# IZU2023_computerboard_ver3.net
KiCad netlist of a schematic drawn in EAGLE
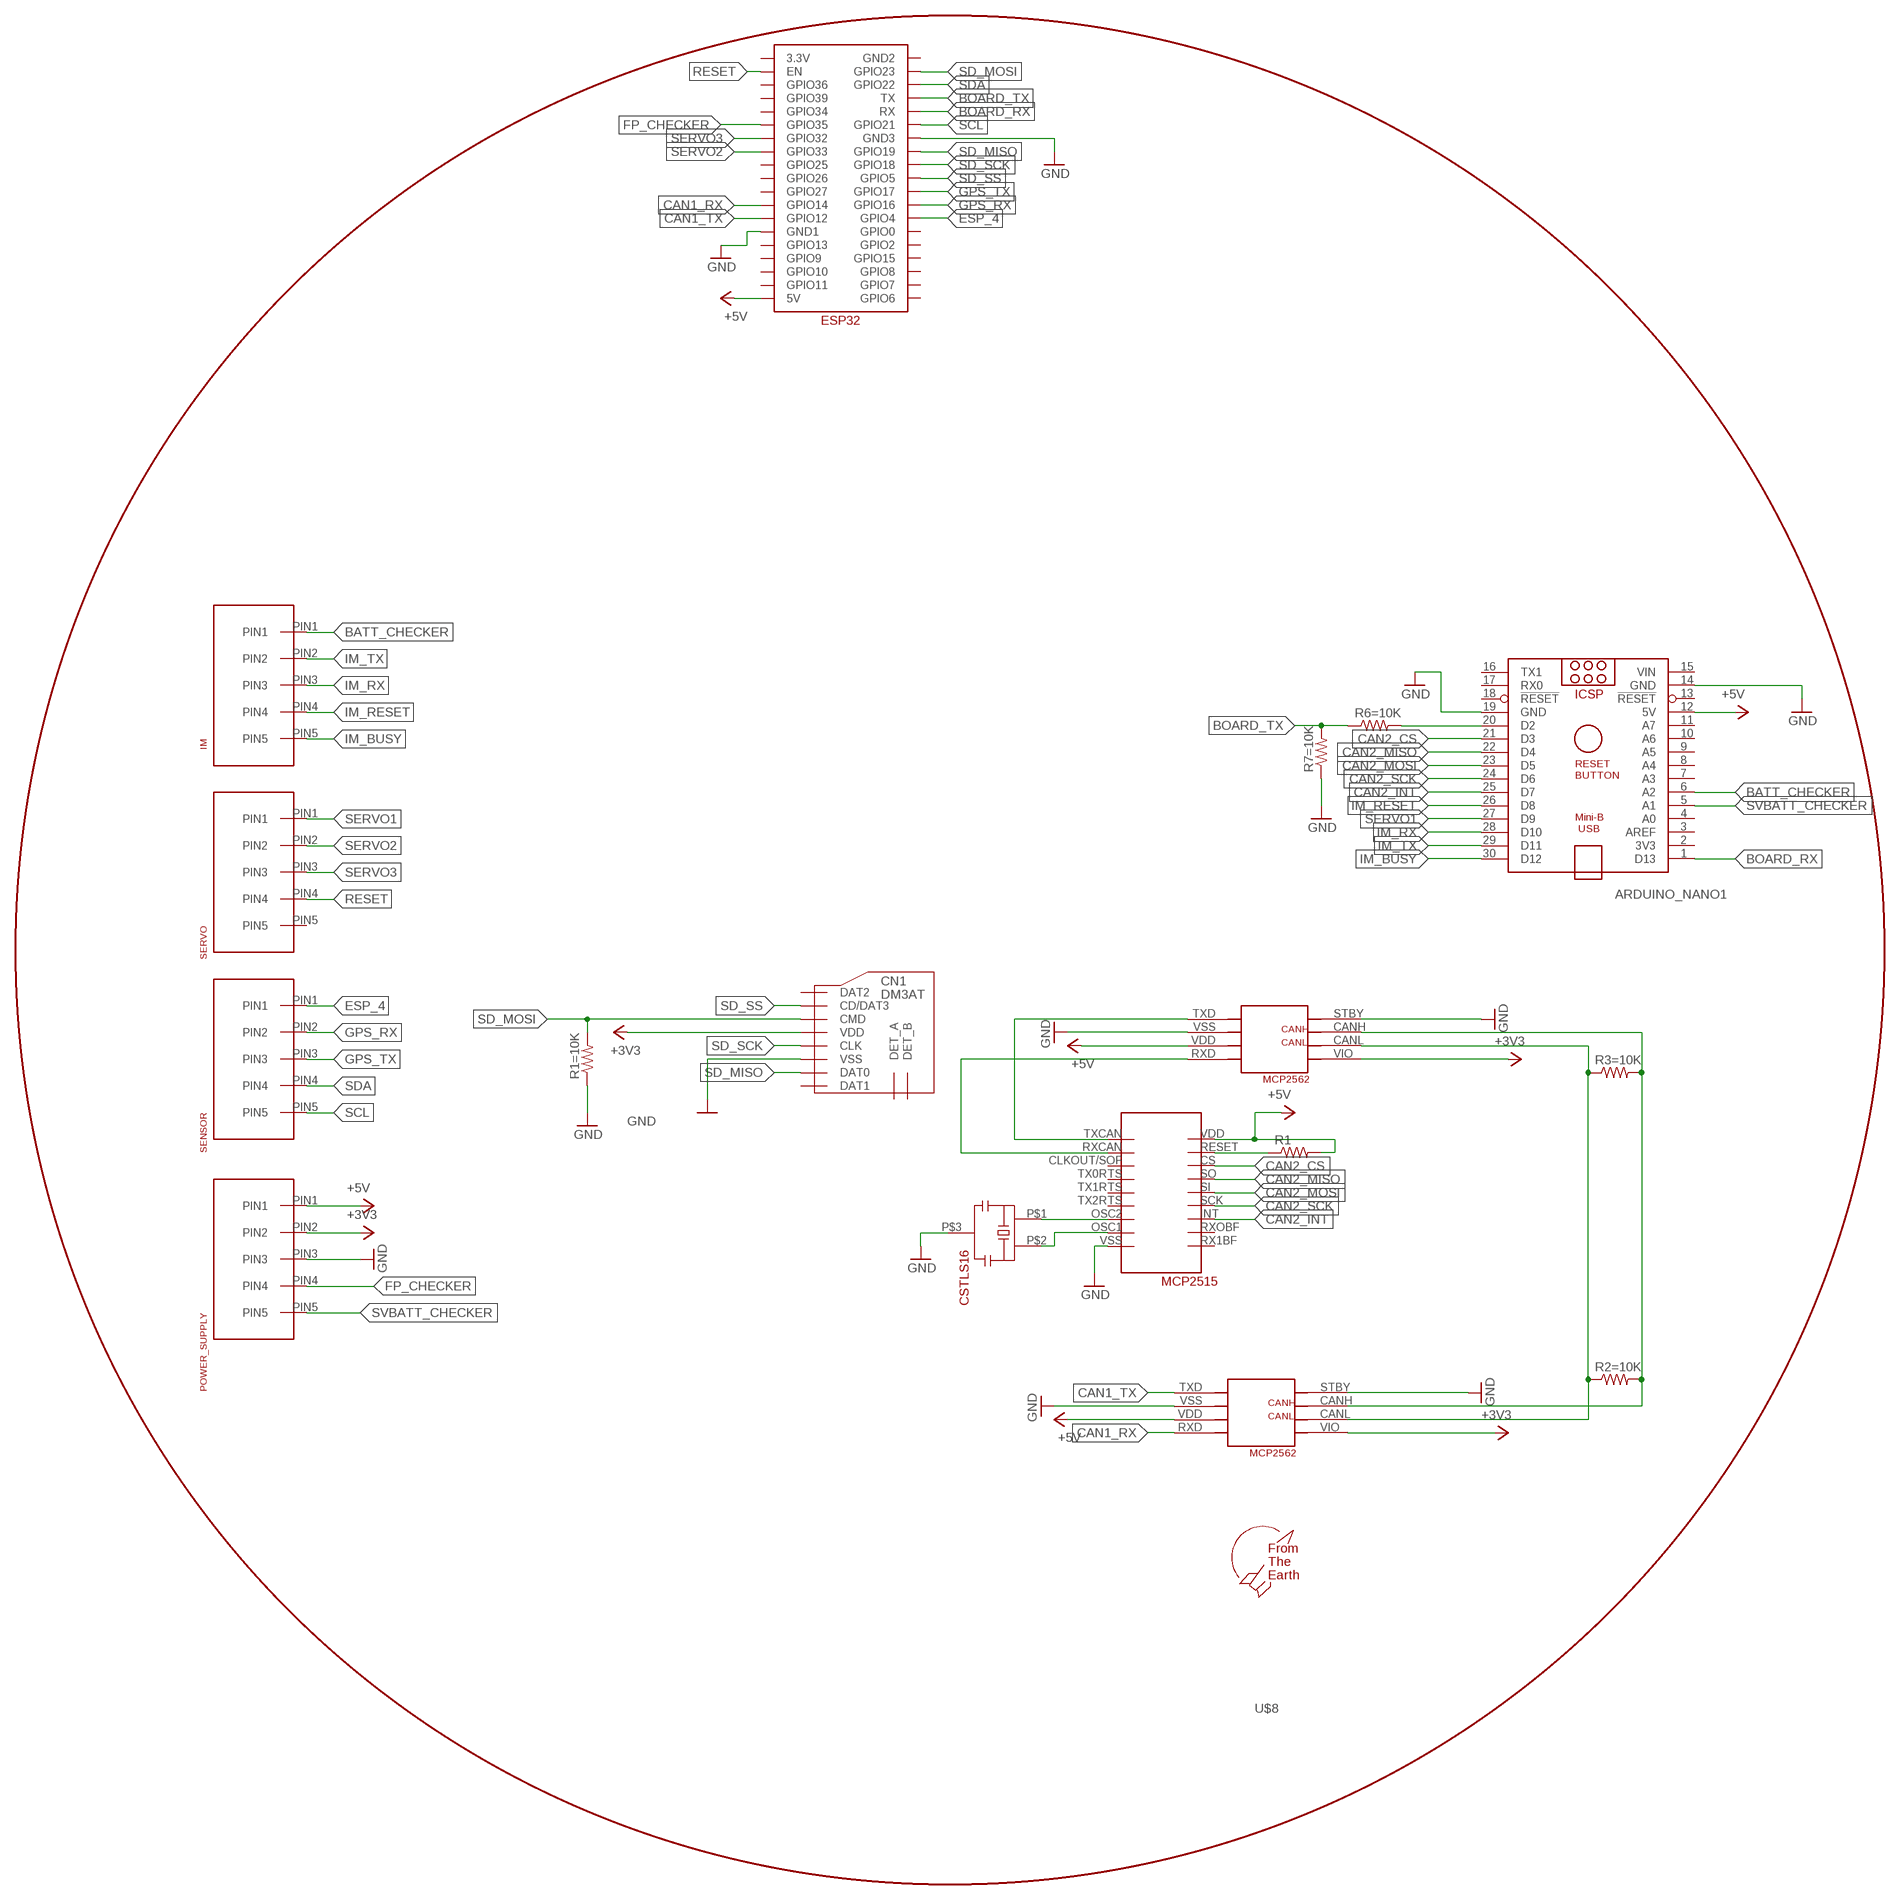
[diagram p0: schematic, sheet 1]

(export (version "E")
  (design (tool "Eeschema 10.0.6"))
  (components
    (comp (ref "ARDUINO_NANO1")
      (value "ARDUINO_NANO")
      (footprint "eagle-import:ARDUINO_NANO")
      (libsource (lib "eagle-import") (part "ARDUINO_NANO"))
    )
    (comp (ref "CN1")
      (value "DM3AT")
      (footprint "eagle-import:DM3AT")
      (libsource (lib "eagle-import") (part "DM3AT"))
    )
    (comp (ref "IM")
      (value "5PIN")
      (footprint "eagle-import:5PIN")
      (libsource (lib "eagle-import") (part "5PIN"))
    )
    (comp (ref "POWER_SUPPLY")
      (value "5PIN")
      (footprint "eagle-import:5PIN")
      (libsource (lib "eagle-import") (part "5PIN"))
    )
    (comp (ref "R1")
      (value "R-US_0204/7")
      (footprint "eagle-import:0204_7")
      (libsource (lib "eagle-import") (part "R-US_0204/7"))
    )
    (comp (ref "R1=10K")
      (value "R-US_0204/7")
      (footprint "eagle-import:0204_7")
      (libsource (lib "eagle-import") (part "R-US_0204/7"))
    )
    (comp (ref "R2=10K")
      (value "R-US_0204/7")
      (footprint "eagle-import:0204_7")
      (libsource (lib "eagle-import") (part "R-US_0204/7"))
    )
    (comp (ref "R3=10K")
      (value "R-US_0204/7")
      (footprint "eagle-import:0204_7")
      (libsource (lib "eagle-import") (part "R-US_0204/7"))
    )
    (comp (ref "R6=10K")
      (value "R-US_0204/7")
      (footprint "eagle-import:0204_7")
      (libsource (lib "eagle-import") (part "R-US_0204/7"))
    )
    (comp (ref "R7=10K")
      (value "R-US_0204/7")
      (footprint "eagle-import:0204_7")
      (libsource (lib "eagle-import") (part "R-US_0204/7"))
    )
    (comp (ref "SENSOR")
      (value "5PIN")
      (footprint "eagle-import:5PIN")
      (libsource (lib "eagle-import") (part "5PIN"))
    )
    (comp (ref "SERVO")
      (value "5PIN")
      (footprint "eagle-import:5PIN")
      (libsource (lib "eagle-import") (part "5PIN"))
    )
    (comp (ref "U$2")
      (value "MCP2515")
      (footprint "eagle-import:MCP2515")
      (libsource (lib "eagle-import") (part "MCP2515"))
    )
    (comp (ref "U$3")
      (value "MCP2562")
      (footprint "eagle-import:MCP2562")
      (libsource (lib "eagle-import") (part "MCP2562"))
    )
    (comp (ref "U$4")
      (value "MCP2562")
      (footprint "eagle-import:MCP2562")
      (libsource (lib "eagle-import") (part "MCP2562"))
    )
    (comp (ref "U$5")
      (value "CSTLS16")
      (footprint "eagle-import:CSTLS16")
      (libsource (lib "eagle-import") (part "CSTLS16"))
    )
    (comp (ref "U$7")
      (value "ESP32_ESP32")
      (footprint "eagle-import:ESP32_ESP32")
      (libsource (lib "eagle-import") (part "ESP32_ESP32"))
    )
    (comp (ref "U$8")
      (value "F.T.E.LOGO")
      (footprint "eagle-import:LOGO")
      (libsource (lib "eagle-import") (part "F.T.E.LOGO"))
    )
  )
  (nets
    (net (code "1") (name "+3V3") (class "Default")
      (node (ref "CN1") (pin "VDD") (pinfunction "VDD_VDD") (pintype "bidirectional"))
      (node (ref "POWER_SUPPLY") (pin "PIN2") (pinfunction "PIN2_PIN2") (pintype "bidirectional"))
      (node (ref "U$3") (pin "VIO") (pinfunction "VIO_VIO") (pintype "bidirectional"))
      (node (ref "U$4") (pin "VIO") (pinfunction "VIO_VIO") (pintype "bidirectional"))
    )
    (net (code "2") (name "+5V") (class "Default")
      (node (ref "ARDUINO_NANO1") (pin "12") (pinfunction "5V_12") (pintype "power_in"))
      (node (ref "POWER_SUPPLY") (pin "PIN1") (pinfunction "PIN1_PIN1") (pintype "bidirectional"))
      (node (ref "R1") (pin "2") (pinfunction "2_2") (pintype "passive"))
      (node (ref "U$2") (pin "VDD") (pinfunction "VDD_VDD") (pintype "bidirectional"))
      (node (ref "U$3") (pin "VDD") (pinfunction "VDD_VDD") (pintype "bidirectional"))
      (node (ref "U$4") (pin "VDD") (pinfunction "VDD_VDD") (pintype "bidirectional"))
      (node (ref "U$7") (pin "5V") (pinfunction "5V_5V") (pintype "bidirectional"))
    )
    (net (code "3") (name "/VIN") (class "Default")
      (node (ref "ARDUINO_NANO1") (pin "15") (pinfunction "VIN_15") (pintype "power_in"))
    )
    (net (code "4") (name "BATT_CHECKER") (class "Default")
      (node (ref "ARDUINO_NANO1") (pin "6") (pinfunction "A2_6") (pintype "bidirectional"))
      (node (ref "IM") (pin "PIN1") (pinfunction "PIN1_PIN1") (pintype "bidirectional"))
    )
    (net (code "5") (name "BOARD_RX") (class "Default")
      (node (ref "ARDUINO_NANO1") (pin "1") (pinfunction "D13_1") (pintype "bidirectional"))
      (node (ref "U$7") (pin "RX") (pinfunction "RX_RX") (pintype "bidirectional"))
    )
    (net (code "6") (name "BOARD_TX") (class "Default")
      (node (ref "R6=10K") (pin "1") (pinfunction "1_1") (pintype "passive"))
      (node (ref "R7=10K") (pin "2") (pinfunction "2_2") (pintype "passive"))
      (node (ref "U$7") (pin "TX") (pinfunction "TX_TX") (pintype "bidirectional"))
    )
    (net (code "7") (name "CAN1_RX") (class "Default")
      (node (ref "U$3") (pin "RXD") (pinfunction "RXD_RXD") (pintype "bidirectional"))
      (node (ref "U$7") (pin "GPIO14") (pinfunction "GPIO14_GPIO14") (pintype "bidirectional"))
    )
    (net (code "8") (name "CAN1_TX") (class "Default")
      (node (ref "U$3") (pin "TXD") (pinfunction "TXD_TXD") (pintype "bidirectional"))
      (node (ref "U$7") (pin "GPIO12") (pinfunction "GPIO12_GPIO12") (pintype "bidirectional"))
    )
    (net (code "9") (name "CAN2_CS") (class "Default")
      (node (ref "ARDUINO_NANO1") (pin "21") (pinfunction "D3_21") (pintype "bidirectional"))
      (node (ref "U$2") (pin "CS") (pinfunction "CS_CS") (pintype "bidirectional"))
    )
    (net (code "10") (name "CAN2_INT") (class "Default")
      (node (ref "ARDUINO_NANO1") (pin "25") (pinfunction "D7_25") (pintype "bidirectional"))
      (node (ref "U$2") (pin "INT") (pinfunction "INT_INT") (pintype "bidirectional"))
    )
    (net (code "11") (name "CAN2_MISO") (class "Default")
      (node (ref "ARDUINO_NANO1") (pin "22") (pinfunction "D4_22") (pintype "bidirectional"))
      (node (ref "U$2") (pin "SO") (pinfunction "SO_SO") (pintype "bidirectional"))
    )
    (net (code "12") (name "CAN2_MOSI") (class "Default")
      (node (ref "ARDUINO_NANO1") (pin "23") (pinfunction "D5_23") (pintype "bidirectional"))
      (node (ref "U$2") (pin "SI") (pinfunction "SI_SI") (pintype "bidirectional"))
    )
    (net (code "13") (name "CAN2_SCK") (class "Default")
      (node (ref "ARDUINO_NANO1") (pin "24") (pinfunction "D6_24") (pintype "bidirectional"))
      (node (ref "U$2") (pin "SCK") (pinfunction "SCK_SCK") (pintype "bidirectional"))
    )
    (net (code "14") (name "ESP_4") (class "Default")
      (node (ref "SENSOR") (pin "PIN1") (pinfunction "PIN1_PIN1") (pintype "bidirectional"))
      (node (ref "U$7") (pin "GPIO4") (pinfunction "GPIO4_GPIO4") (pintype "bidirectional"))
    )
    (net (code "15") (name "FP_CHECKER") (class "Default")
      (node (ref "POWER_SUPPLY") (pin "PIN4") (pinfunction "PIN4_PIN4") (pintype "bidirectional"))
      (node (ref "U$7") (pin "GPIO35") (pinfunction "GPIO35_GPIO35") (pintype "bidirectional"))
    )
    (net (code "16") (name "GND") (class "Default")
      (node (ref "ARDUINO_NANO1") (pin "14") (pinfunction "GND_14") (pintype "power_in"))
      (node (ref "ARDUINO_NANO1") (pin "19") (pinfunction "GND_19") (pintype "power_in"))
      (node (ref "CN1") (pin "VSS") (pinfunction "VSS_VSS") (pintype "bidirectional"))
      (node (ref "POWER_SUPPLY") (pin "PIN3") (pinfunction "PIN3_PIN3") (pintype "bidirectional"))
      (node (ref "R1=10K") (pin "1") (pinfunction "1_1") (pintype "passive"))
      (node (ref "R7=10K") (pin "1") (pinfunction "1_1") (pintype "passive"))
      (node (ref "U$2") (pin "VSS") (pinfunction "VSS_VSS") (pintype "bidirectional"))
      (node (ref "U$3") (pin "STBY") (pinfunction "STBY_STBY") (pintype "bidirectional"))
      (node (ref "U$3") (pin "VSS") (pinfunction "VSS_VSS") (pintype "bidirectional"))
      (node (ref "U$4") (pin "STBY") (pinfunction "STBY_STBY") (pintype "bidirectional"))
      (node (ref "U$4") (pin "VSS") (pinfunction "VSS_VSS") (pintype "bidirectional"))
      (node (ref "U$5") (pin "P$3") (pinfunction "P$3_P$3") (pintype "bidirectional"))
      (node (ref "U$7") (pin "GND1") (pinfunction "GND1_GND1") (pintype "bidirectional"))
      (node (ref "U$7") (pin "GND3") (pinfunction "GND3_GND3") (pintype "bidirectional"))
    )
    (net (code "17") (name "GPS_RX") (class "Default")
      (node (ref "SENSOR") (pin "PIN2") (pinfunction "PIN2_PIN2") (pintype "bidirectional"))
      (node (ref "U$7") (pin "GPIO16") (pinfunction "GPIO16_GPIO16") (pintype "bidirectional"))
    )
    (net (code "18") (name "GPS_TX") (class "Default")
      (node (ref "SENSOR") (pin "PIN3") (pinfunction "PIN3_PIN3") (pintype "bidirectional"))
      (node (ref "U$7") (pin "GPIO17") (pinfunction "GPIO17_GPIO17") (pintype "bidirectional"))
    )
    (net (code "19") (name "IM_BUSY") (class "Default")
      (node (ref "ARDUINO_NANO1") (pin "30") (pinfunction "D12_30") (pintype "bidirectional"))
      (node (ref "IM") (pin "PIN5") (pinfunction "PIN5_PIN5") (pintype "bidirectional"))
    )
    (net (code "20") (name "IM_RESET") (class "Default")
      (node (ref "ARDUINO_NANO1") (pin "26") (pinfunction "D8_26") (pintype "bidirectional"))
      (node (ref "IM") (pin "PIN4") (pinfunction "PIN4_PIN4") (pintype "bidirectional"))
    )
    (net (code "21") (name "IM_RX") (class "Default")
      (node (ref "ARDUINO_NANO1") (pin "28") (pinfunction "D10_28") (pintype "bidirectional"))
      (node (ref "IM") (pin "PIN3") (pinfunction "PIN3_PIN3") (pintype "bidirectional"))
    )
    (net (code "22") (name "IM_TX") (class "Default")
      (node (ref "ARDUINO_NANO1") (pin "29") (pinfunction "D11_29") (pintype "bidirectional"))
      (node (ref "IM") (pin "PIN2") (pinfunction "PIN2_PIN2") (pintype "bidirectional"))
    )
    (net (code "23") (name "Net-(ARDUINO_NANO1-D2)") (class "Default")
      (node (ref "ARDUINO_NANO1") (pin "20") (pinfunction "D2_20") (pintype "bidirectional"))
      (node (ref "R6=10K") (pin "2") (pinfunction "2_2") (pintype "passive"))
    )
    (net (code "24") (name "Net-(R1-Pad1)") (class "Default")
      (node (ref "R1") (pin "1") (pinfunction "1_1") (pintype "passive"))
      (node (ref "U$2") (pin "RESET") (pinfunction "RESET_RESET") (pintype "bidirectional"))
    )
    (net (code "25") (name "Net-(R2=10K-Pad1)") (class "Default")
      (node (ref "R2=10K") (pin "1") (pinfunction "1_1") (pintype "passive"))
      (node (ref "R3=10K") (pin "1") (pinfunction "1_1") (pintype "passive"))
      (node (ref "U$3") (pin "CANL") (pinfunction "CANL_CANL") (pintype "bidirectional"))
      (node (ref "U$4") (pin "CANL") (pinfunction "CANL_CANL") (pintype "bidirectional"))
    )
    (net (code "26") (name "Net-(R2=10K-Pad2)") (class "Default")
      (node (ref "R2=10K") (pin "2") (pinfunction "2_2") (pintype "passive"))
      (node (ref "R3=10K") (pin "2") (pinfunction "2_2") (pintype "passive"))
      (node (ref "U$3") (pin "CANH") (pinfunction "CANH_CANH") (pintype "bidirectional"))
      (node (ref "U$4") (pin "CANH") (pinfunction "CANH_CANH") (pintype "bidirectional"))
    )
    (net (code "27") (name "Net-(U$2-PadOSC1)") (class "Default")
      (node (ref "U$2") (pin "OSC1") (pinfunction "OSC1_OSC1") (pintype "bidirectional"))
      (node (ref "U$5") (pin "P$2") (pinfunction "P$2_P$2") (pintype "bidirectional"))
    )
    (net (code "28") (name "Net-(U$2-PadOSC2)") (class "Default")
      (node (ref "U$2") (pin "OSC2") (pinfunction "OSC2_OSC2") (pintype "bidirectional"))
      (node (ref "U$5") (pin "P$1") (pinfunction "P$1_P$1") (pintype "bidirectional"))
    )
    (net (code "29") (name "Net-(U$2-PadRXCAN)") (class "Default")
      (node (ref "U$2") (pin "RXCAN") (pinfunction "RXCAN_RXCAN") (pintype "bidirectional"))
      (node (ref "U$4") (pin "RXD") (pinfunction "RXD_RXD") (pintype "bidirectional"))
    )
    (net (code "30") (name "Net-(U$2-PadTXCAN)") (class "Default")
      (node (ref "U$2") (pin "TXCAN") (pinfunction "TXCAN_TXCAN") (pintype "bidirectional"))
      (node (ref "U$4") (pin "TXD") (pinfunction "TXD_TXD") (pintype "bidirectional"))
    )
    (net (code "31") (name "RESET") (class "Default")
      (node (ref "SERVO") (pin "PIN4") (pinfunction "PIN4_PIN4") (pintype "bidirectional"))
      (node (ref "U$7") (pin "EN") (pinfunction "EN_EN") (pintype "bidirectional"))
    )
    (net (code "32") (name "SCL") (class "Default")
      (node (ref "SENSOR") (pin "PIN5") (pinfunction "PIN5_PIN5") (pintype "bidirectional"))
      (node (ref "U$7") (pin "GPIO21") (pinfunction "GPIO21_GPIO21") (pintype "bidirectional"))
    )
    (net (code "33") (name "SDA") (class "Default")
      (node (ref "SENSOR") (pin "PIN4") (pinfunction "PIN4_PIN4") (pintype "bidirectional"))
      (node (ref "U$7") (pin "GPIO22") (pinfunction "GPIO22_GPIO22") (pintype "bidirectional"))
    )
    (net (code "34") (name "SD_MISO") (class "Default")
      (node (ref "CN1") (pin "DAT0") (pinfunction "DAT0_DAT0") (pintype "bidirectional"))
      (node (ref "U$7") (pin "GPIO19") (pinfunction "GPIO19_GPIO19") (pintype "bidirectional"))
    )
    (net (code "35") (name "SD_MOSI") (class "Default")
      (node (ref "CN1") (pin "CMD") (pinfunction "CMD_CMD") (pintype "bidirectional"))
      (node (ref "R1=10K") (pin "2") (pinfunction "2_2") (pintype "passive"))
      (node (ref "U$7") (pin "GPIO23") (pinfunction "GPIO23_GPIO23") (pintype "bidirectional"))
    )
    (net (code "36") (name "SD_SCK") (class "Default")
      (node (ref "CN1") (pin "CLK") (pinfunction "CLK_CLK") (pintype "bidirectional"))
      (node (ref "U$7") (pin "GPIO18") (pinfunction "GPIO18_GPIO18") (pintype "bidirectional"))
    )
    (net (code "37") (name "SD_SS") (class "Default")
      (node (ref "CN1") (pin "CD/DAT3") (pinfunction "CD/DAT3_CD/DAT3") (pintype "bidirectional"))
      (node (ref "U$7") (pin "GPIO5") (pinfunction "GPIO5_GPIO5") (pintype "bidirectional"))
    )
    (net (code "38") (name "SERVO1") (class "Default")
      (node (ref "ARDUINO_NANO1") (pin "27") (pinfunction "D9_27") (pintype "bidirectional"))
      (node (ref "SERVO") (pin "PIN1") (pinfunction "PIN1_PIN1") (pintype "bidirectional"))
    )
    (net (code "39") (name "SERVO2") (class "Default")
      (node (ref "SERVO") (pin "PIN2") (pinfunction "PIN2_PIN2") (pintype "bidirectional"))
      (node (ref "U$7") (pin "GPIO33") (pinfunction "GPIO33_GPIO33") (pintype "bidirectional"))
    )
    (net (code "40") (name "SERVO3") (class "Default")
      (node (ref "SERVO") (pin "PIN3") (pinfunction "PIN3_PIN3") (pintype "bidirectional"))
      (node (ref "U$7") (pin "GPIO32") (pinfunction "GPIO32_GPIO32") (pintype "bidirectional"))
    )
    (net (code "41") (name "SVBATT_CHECKER") (class "Default")
      (node (ref "ARDUINO_NANO1") (pin "5") (pinfunction "A1_5") (pintype "bidirectional"))
      (node (ref "POWER_SUPPLY") (pin "PIN5") (pinfunction "PIN5_PIN5") (pintype "bidirectional"))
    )
    (net (code "42") (name "unconnected-(ARDUINO_NANO1-3V3-Pad2)") (class "Default")
      (node (ref "ARDUINO_NANO1") (pin "2") (pinfunction "3V3_2") (pintype "output"))
    )
    (net (code "43") (name "unconnected-(ARDUINO_NANO1-A0-Pad4)") (class "Default")
      (node (ref "ARDUINO_NANO1") (pin "4") (pinfunction "A0_4") (pintype "bidirectional"))
    )
    (net (code "44") (name "unconnected-(ARDUINO_NANO1-A3-Pad7)") (class "Default")
      (node (ref "ARDUINO_NANO1") (pin "7") (pinfunction "A3_7") (pintype "bidirectional"))
    )
    (net (code "45") (name "unconnected-(ARDUINO_NANO1-A4-Pad8)") (class "Default")
      (node (ref "ARDUINO_NANO1") (pin "8") (pinfunction "A4_8") (pintype "bidirectional"))
    )
    (net (code "46") (name "unconnected-(ARDUINO_NANO1-A5-Pad9)") (class "Default")
      (node (ref "ARDUINO_NANO1") (pin "9") (pinfunction "A5_9") (pintype "bidirectional"))
    )
    (net (code "47") (name "unconnected-(ARDUINO_NANO1-A6-Pad10)") (class "Default")
      (node (ref "ARDUINO_NANO1") (pin "10") (pinfunction "A6_10") (pintype "bidirectional"))
    )
    (net (code "48") (name "unconnected-(ARDUINO_NANO1-A7-Pad11)") (class "Default")
      (node (ref "ARDUINO_NANO1") (pin "11") (pinfunction "A7_11") (pintype "bidirectional"))
    )
    (net (code "49") (name "unconnected-(ARDUINO_NANO1-AREF-Pad3)") (class "Default")
      (node (ref "ARDUINO_NANO1") (pin "3") (pinfunction "AREF_3") (pintype "input"))
    )
    (net (code "50") (name "unconnected-(ARDUINO_NANO1-RX0-Pad17)") (class "Default")
      (node (ref "ARDUINO_NANO1") (pin "17") (pinfunction "RX0_17") (pintype "bidirectional"))
    )
    (net (code "51") (name "unconnected-(ARDUINO_NANO1-TX1-Pad16)") (class "Default")
      (node (ref "ARDUINO_NANO1") (pin "16") (pinfunction "TX1_16") (pintype "bidirectional"))
    )
    (net (code "52") (name "unconnected-(ARDUINO_NANO1-~{RESET}-Pad13)") (class "Default")
      (node (ref "ARDUINO_NANO1") (pin "13") (pinfunction "~{RESET}_13") (pintype "input"))
    )
    (net (code "53") (name "unconnected-(ARDUINO_NANO1-~{RESET}-Pad18)") (class "Default")
      (node (ref "ARDUINO_NANO1") (pin "18") (pinfunction "~{RESET}_18") (pintype "input"))
    )
    (net (code "54") (name "unconnected-(CN1-PadDAT1)") (class "Default")
      (node (ref "CN1") (pin "DAT1") (pinfunction "DAT1_DAT1") (pintype "bidirectional"))
    )
    (net (code "55") (name "unconnected-(CN1-PadDAT2)") (class "Default")
      (node (ref "CN1") (pin "DAT2") (pinfunction "DAT2_DAT2") (pintype "bidirectional"))
    )
    (net (code "56") (name "unconnected-(CN1-PadDET_A)") (class "Default")
      (node (ref "CN1") (pin "DET_A") (pinfunction "DET_A_DET_A") (pintype "bidirectional"))
    )
    (net (code "57") (name "unconnected-(CN1-PadDET_B)") (class "Default")
      (node (ref "CN1") (pin "DET_B") (pinfunction "DET_B_DET_B") (pintype "bidirectional"))
    )
    (net (code "58") (name "unconnected-(SERVO-PadPIN5)") (class "Default")
      (node (ref "SERVO") (pin "PIN5") (pinfunction "PIN5_PIN5") (pintype "bidirectional"))
    )
    (net (code "59") (name "unconnected-(U$2-PadCLKOUT{slash}SOF)") (class "Default")
      (node (ref "U$2") (pin "CLKOUT/SOF") (pinfunction "CLKOUT/SOF_CLKOUT/SOF") (pintype "bidirectional"))
    )
    (net (code "60") (name "unconnected-(U$2-PadRX1BF)") (class "Default")
      (node (ref "U$2") (pin "RX1BF") (pinfunction "RX1BF_RX1BF") (pintype "bidirectional"))
    )
    (net (code "61") (name "unconnected-(U$2-PadTX0RTS)") (class "Default")
      (node (ref "U$2") (pin "TX0RTS") (pinfunction "TX0RTS_TX0RTS") (pintype "bidirectional"))
    )
    (net (code "62") (name "unconnected-(U$2-PadTX1RTS)") (class "Default")
      (node (ref "U$2") (pin "TX1RTS") (pinfunction "TX1RTS_TX1RTS") (pintype "bidirectional"))
    )
    (net (code "63") (name "unconnected-(U$2-PadTX2RTS)") (class "Default")
      (node (ref "U$2") (pin "TX2RTS") (pinfunction "TX2RTS_TX2RTS") (pintype "bidirectional"))
    )
    (net (code "64") (name "unconnected-(U$2-RX0BF-PadRXOBF)") (class "Default")
      (node (ref "U$2") (pin "RXOBF") (pinfunction "RX0BF_RXOBF") (pintype "bidirectional"))
    )
    (net (code "65") (name "unconnected-(U$7-Pad3.3V)") (class "Default")
      (node (ref "U$7") (pin "3.3V") (pinfunction "3.3V_3.3V") (pintype "bidirectional"))
    )
    (net (code "66") (name "unconnected-(U$7-PadGND2)") (class "Default")
      (node (ref "U$7") (pin "GND2") (pinfunction "GND2_GND2") (pintype "bidirectional"))
    )
    (net (code "67") (name "unconnected-(U$7-PadGPIO0)") (class "Default")
      (node (ref "U$7") (pin "GPIO0") (pinfunction "GPIO0_GPIO0") (pintype "bidirectional"))
    )
    (net (code "68") (name "unconnected-(U$7-PadGPIO2)") (class "Default")
      (node (ref "U$7") (pin "GPIO2") (pinfunction "GPIO2_GPIO2") (pintype "bidirectional"))
    )
    (net (code "69") (name "unconnected-(U$7-PadGPIO6)") (class "Default")
      (node (ref "U$7") (pin "GPIO6") (pinfunction "GPIO6_GPIO6") (pintype "bidirectional"))
    )
    (net (code "70") (name "unconnected-(U$7-PadGPIO7)") (class "Default")
      (node (ref "U$7") (pin "GPIO7") (pinfunction "GPIO7_GPIO7") (pintype "bidirectional"))
    )
    (net (code "71") (name "unconnected-(U$7-PadGPIO8)") (class "Default")
      (node (ref "U$7") (pin "GPIO8") (pinfunction "GPIO8_GPIO8") (pintype "bidirectional"))
    )
    (net (code "72") (name "unconnected-(U$7-PadGPIO9)") (class "Default")
      (node (ref "U$7") (pin "GPIO9") (pinfunction "GPIO9_GPIO9") (pintype "bidirectional"))
    )
    (net (code "73") (name "unconnected-(U$7-PadGPIO10)") (class "Default")
      (node (ref "U$7") (pin "GPIO10") (pinfunction "GPIO10_GPIO10") (pintype "bidirectional"))
    )
    (net (code "74") (name "unconnected-(U$7-PadGPIO11)") (class "Default")
      (node (ref "U$7") (pin "GPIO11") (pinfunction "GPIO11_GPIO11") (pintype "bidirectional"))
    )
    (net (code "75") (name "unconnected-(U$7-PadGPIO13)") (class "Default")
      (node (ref "U$7") (pin "GPIO13") (pinfunction "GPIO13_GPIO13") (pintype "bidirectional"))
    )
    (net (code "76") (name "unconnected-(U$7-PadGPIO15)") (class "Default")
      (node (ref "U$7") (pin "GPIO15") (pinfunction "GPIO15_GPIO15") (pintype "bidirectional"))
    )
    (net (code "77") (name "unconnected-(U$7-PadGPIO25)") (class "Default")
      (node (ref "U$7") (pin "GPIO25") (pinfunction "GPIO25_GPIO25") (pintype "bidirectional"))
    )
    (net (code "78") (name "unconnected-(U$7-PadGPIO26)") (class "Default")
      (node (ref "U$7") (pin "GPIO26") (pinfunction "GPIO26_GPIO26") (pintype "bidirectional"))
    )
    (net (code "79") (name "unconnected-(U$7-PadGPIO27)") (class "Default")
      (node (ref "U$7") (pin "GPIO27") (pinfunction "GPIO27_GPIO27") (pintype "bidirectional"))
    )
    (net (code "80") (name "unconnected-(U$7-PadGPIO34)") (class "Default")
      (node (ref "U$7") (pin "GPIO34") (pinfunction "GPIO34_GPIO34") (pintype "bidirectional"))
    )
    (net (code "81") (name "unconnected-(U$7-PadGPIO36)") (class "Default")
      (node (ref "U$7") (pin "GPIO36") (pinfunction "GPIO36_GPIO36") (pintype "bidirectional"))
    )
    (net (code "82") (name "unconnected-(U$7-PadGPIO39)") (class "Default")
      (node (ref "U$7") (pin "GPIO39") (pinfunction "GPIO39_GPIO39") (pintype "bidirectional"))
    )
  )
)
